# IPM_12V_12V.net
KiCad netlist of a schematic drawn in EasyEDA Pro
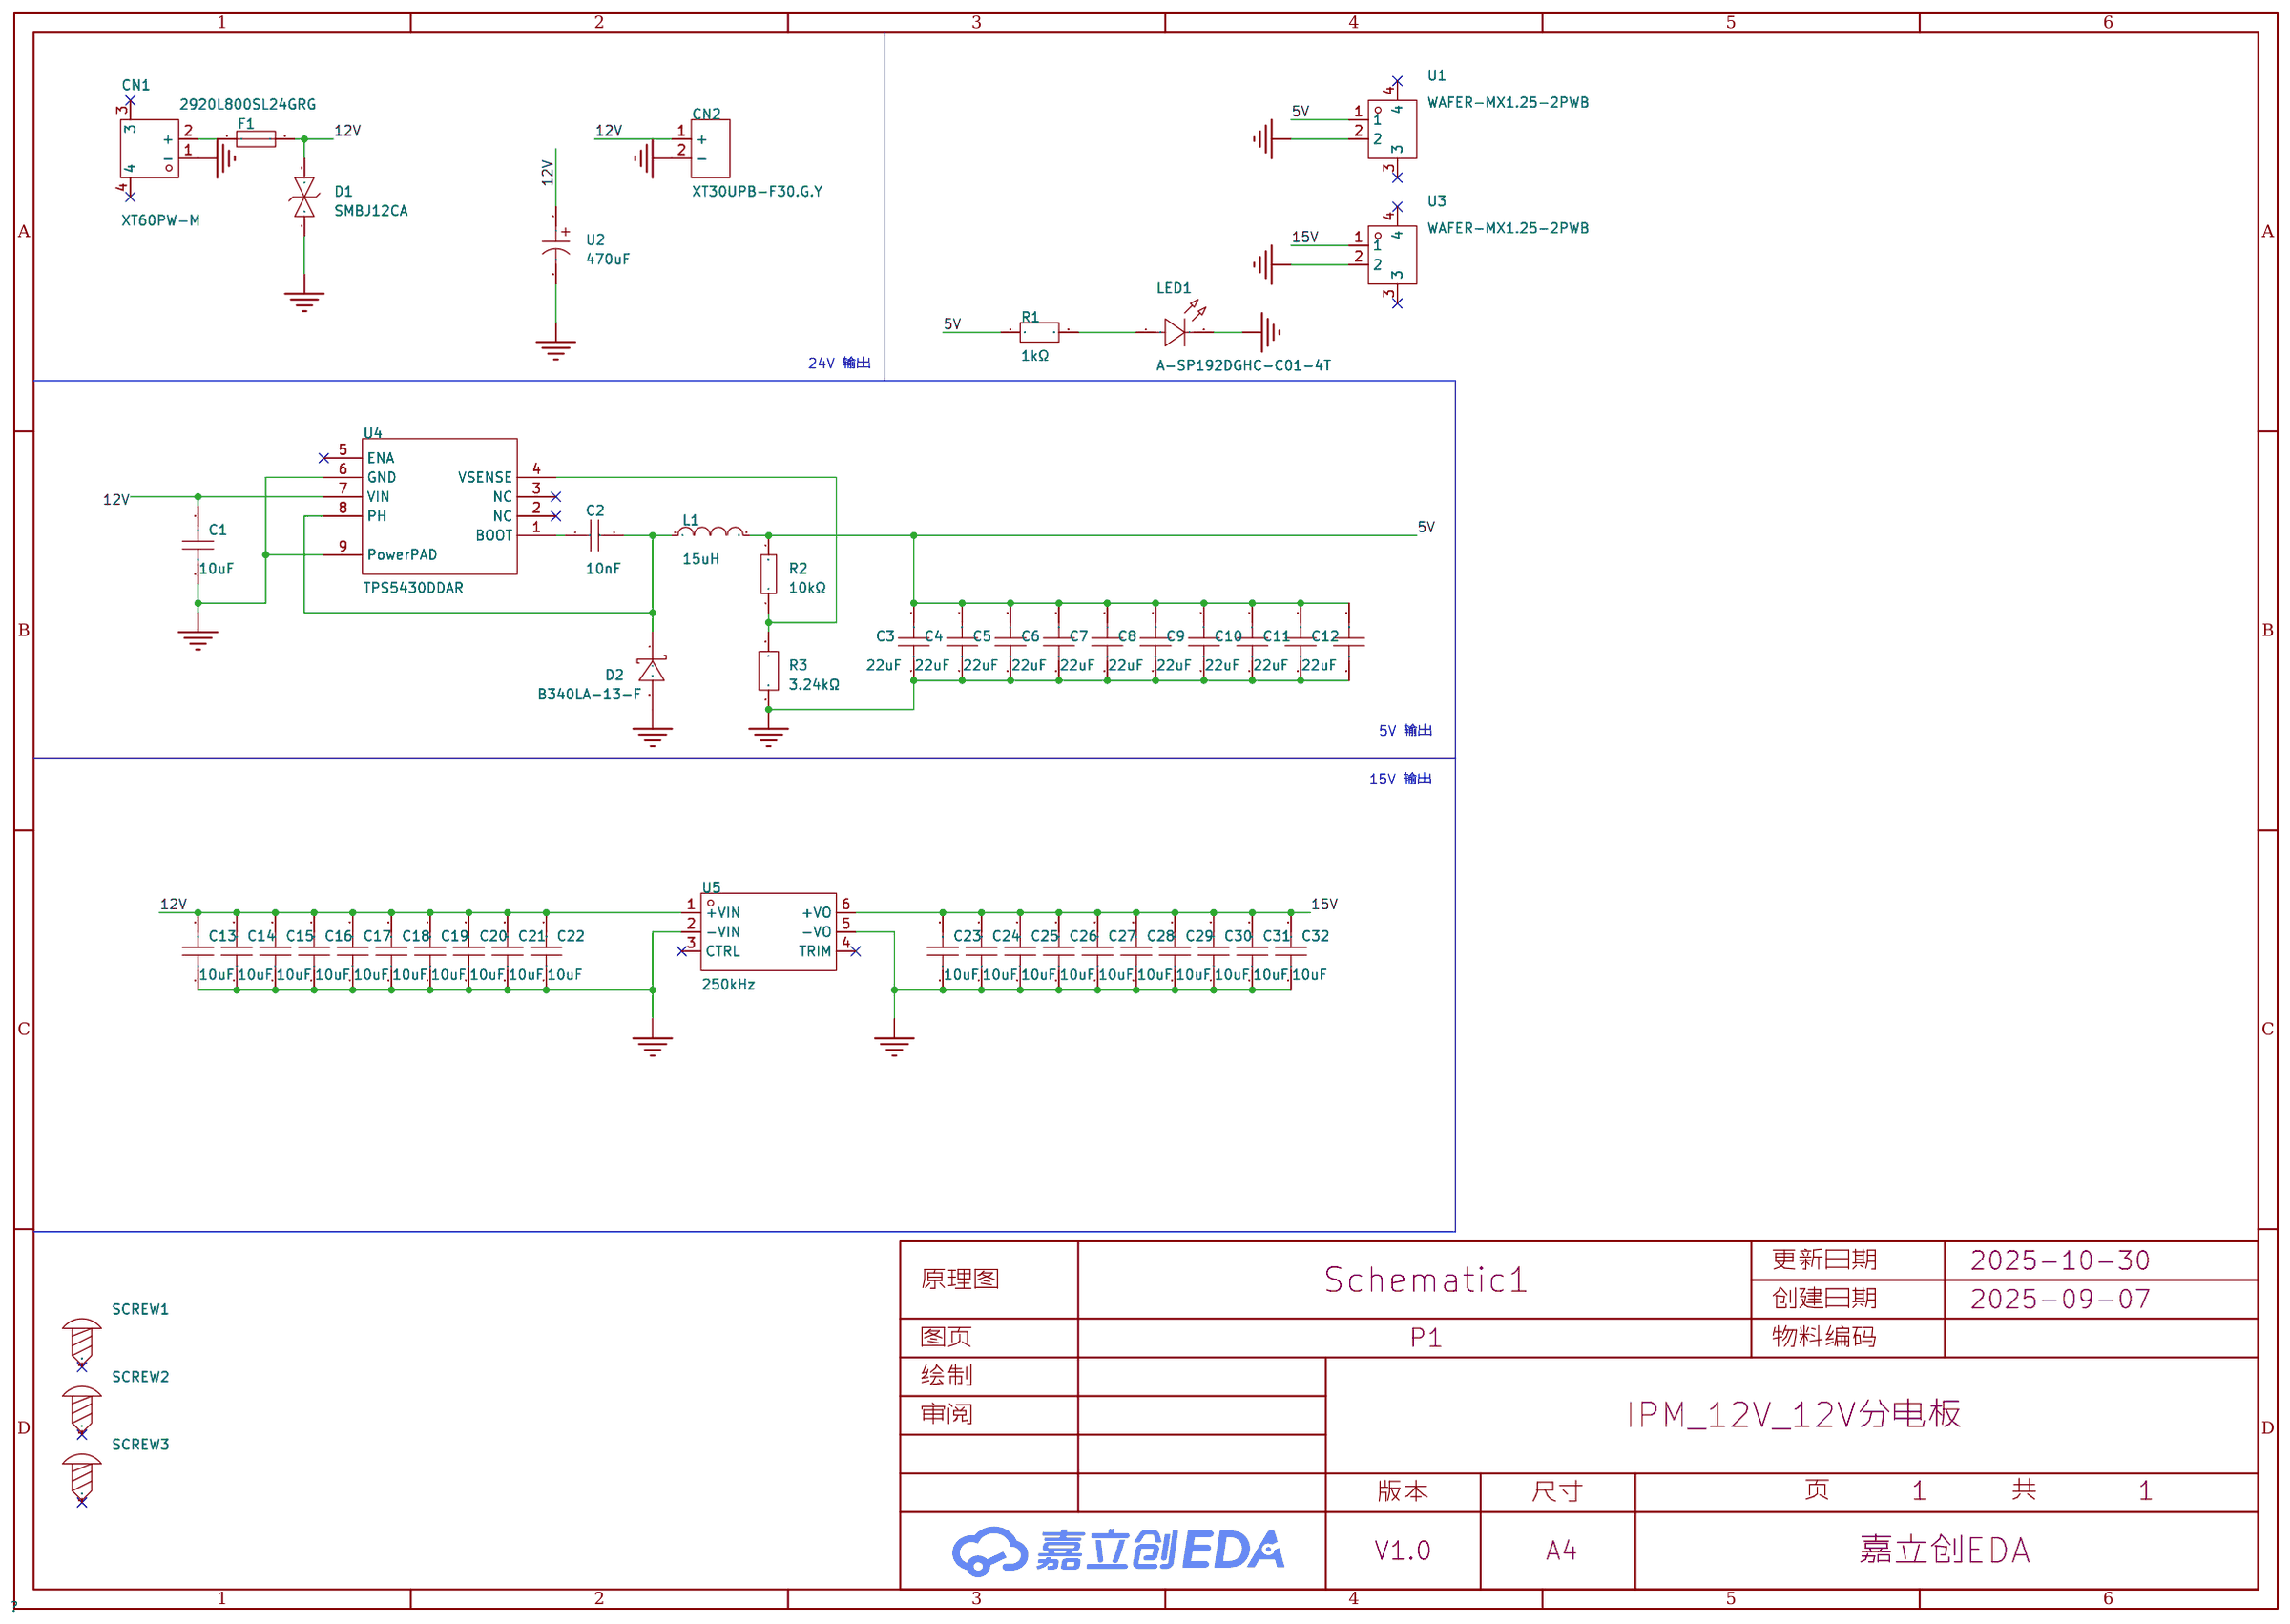
[diagram p0: schematic sheet]

(export (version "E")
  (design (tool "Eeschema 10.0.6"))
  (components
    (comp (ref "C1")
      (value "10uF")
      (footprint "easyedapro:C1206")
      (description "容值:10uF;精度:±10%;额定电压:50V;温度系数:X7R;")
      (fields
        (field (name "Manufacturer Part") "CL31B106KBHNNNE")
        (field (name "Manufacturer") "SAMSUNG(三星)")
      )
      (libsource (lib "easyedapro") (part "CL31B106KBHNNNE"))
    )
    (comp (ref "C2")
      (value "10nF")
      (footprint "easyedapro:C0603")
      (description "容值:10nF;精度:±10%;额定电压:50V;温度系数:X7R;")
      (fields
        (field (name "Manufacturer Part") "CL10B103KB8NNNC")
        (field (name "Manufacturer") "SAMSUNG(三星)")
      )
      (libsource (lib "easyedapro") (part "CL10B103KB8NNNC"))
    )
    (comp (ref "C3")
      (value "22uF")
      (footprint "easyedapro:C0603")
      (description "容值:22uF;精度:±20%;额定电压:16V;温度系数:X5R;")
      (fields
        (field (name "Manufacturer Part") "CL10A226MO7JZNC")
        (field (name "Manufacturer") "SAMSUNG(三星)")
      )
      (libsource (lib "easyedapro") (part "CL10A226MO7JZNC"))
    )
    (comp (ref "C4")
      (value "22uF")
      (footprint "easyedapro:C0603")
      (description "容值:22uF;精度:±20%;额定电压:16V;温度系数:X5R;")
      (fields
        (field (name "Manufacturer Part") "CL10A226MO7JZNC")
        (field (name "Manufacturer") "SAMSUNG(三星)")
      )
      (libsource (lib "easyedapro") (part "CL10A226MO7JZNC"))
    )
    (comp (ref "C5")
      (value "22uF")
      (footprint "easyedapro:C0603")
      (description "容值:22uF;精度:±20%;额定电压:16V;温度系数:X5R;")
      (fields
        (field (name "Manufacturer Part") "CL10A226MO7JZNC")
        (field (name "Manufacturer") "SAMSUNG(三星)")
      )
      (libsource (lib "easyedapro") (part "CL10A226MO7JZNC"))
    )
    (comp (ref "C6")
      (value "22uF")
      (footprint "easyedapro:C0603")
      (description "容值:22uF;精度:±20%;额定电压:16V;温度系数:X5R;")
      (fields
        (field (name "Manufacturer Part") "CL10A226MO7JZNC")
        (field (name "Manufacturer") "SAMSUNG(三星)")
      )
      (libsource (lib "easyedapro") (part "CL10A226MO7JZNC"))
    )
    (comp (ref "C7")
      (value "22uF")
      (footprint "easyedapro:C0603")
      (description "容值:22uF;精度:±20%;额定电压:16V;温度系数:X5R;")
      (fields
        (field (name "Manufacturer Part") "CL10A226MO7JZNC")
        (field (name "Manufacturer") "SAMSUNG(三星)")
      )
      (libsource (lib "easyedapro") (part "CL10A226MO7JZNC"))
    )
    (comp (ref "C8")
      (value "22uF")
      (footprint "easyedapro:C0603")
      (description "容值:22uF;精度:±20%;额定电压:16V;温度系数:X5R;")
      (fields
        (field (name "Manufacturer Part") "CL10A226MO7JZNC")
        (field (name "Manufacturer") "SAMSUNG(三星)")
      )
      (libsource (lib "easyedapro") (part "CL10A226MO7JZNC"))
    )
    (comp (ref "C9")
      (value "22uF")
      (footprint "easyedapro:C0603")
      (description "容值:22uF;精度:±20%;额定电压:16V;温度系数:X5R;")
      (fields
        (field (name "Manufacturer Part") "CL10A226MO7JZNC")
        (field (name "Manufacturer") "SAMSUNG(三星)")
      )
      (libsource (lib "easyedapro") (part "CL10A226MO7JZNC"))
    )
    (comp (ref "C10")
      (value "22uF")
      (footprint "easyedapro:C0603")
      (description "容值:22uF;精度:±20%;额定电压:16V;温度系数:X5R;")
      (fields
        (field (name "Manufacturer Part") "CL10A226MO7JZNC")
        (field (name "Manufacturer") "SAMSUNG(三星)")
      )
      (libsource (lib "easyedapro") (part "CL10A226MO7JZNC"))
    )
    (comp (ref "C11")
      (value "22uF")
      (footprint "easyedapro:C0603")
      (description "容值:22uF;精度:±20%;额定电压:16V;温度系数:X5R;")
      (fields
        (field (name "Manufacturer Part") "CL10A226MO7JZNC")
        (field (name "Manufacturer") "SAMSUNG(三星)")
      )
      (libsource (lib "easyedapro") (part "CL10A226MO7JZNC"))
    )
    (comp (ref "C12")
      (value "22uF")
      (footprint "easyedapro:C0603")
      (description "容值:22uF;精度:±20%;额定电压:16V;温度系数:X5R;")
      (fields
        (field (name "Manufacturer Part") "CL10A226MO7JZNC")
        (field (name "Manufacturer") "SAMSUNG(三星)")
      )
      (libsource (lib "easyedapro") (part "CL10A226MO7JZNC"))
    )
    (comp (ref "C13")
      (value "10uF")
      (footprint "easyedapro:C1206")
      (description "容值:10uF;精度:±10%;额定电压:50V;温度系数:X7R;")
      (fields
        (field (name "Manufacturer Part") "CL31B106KBHNNNE")
        (field (name "Manufacturer") "SAMSUNG(三星)")
      )
      (libsource (lib "easyedapro") (part "CL31B106KBHNNNE"))
    )
    (comp (ref "C14")
      (value "10uF")
      (footprint "easyedapro:C1206")
      (description "容值:10uF;精度:±10%;额定电压:50V;温度系数:X7R;")
      (fields
        (field (name "Manufacturer Part") "CL31B106KBHNNNE")
        (field (name "Manufacturer") "SAMSUNG(三星)")
      )
      (libsource (lib "easyedapro") (part "CL31B106KBHNNNE"))
    )
    (comp (ref "C15")
      (value "10uF")
      (footprint "easyedapro:C1206")
      (description "容值:10uF;精度:±10%;额定电压:50V;温度系数:X7R;")
      (fields
        (field (name "Manufacturer Part") "CL31B106KBHNNNE")
        (field (name "Manufacturer") "SAMSUNG(三星)")
      )
      (libsource (lib "easyedapro") (part "CL31B106KBHNNNE"))
    )
    (comp (ref "C16")
      (value "10uF")
      (footprint "easyedapro:C1206")
      (description "容值:10uF;精度:±10%;额定电压:50V;温度系数:X7R;")
      (fields
        (field (name "Manufacturer Part") "CL31B106KBHNNNE")
        (field (name "Manufacturer") "SAMSUNG(三星)")
      )
      (libsource (lib "easyedapro") (part "CL31B106KBHNNNE"))
    )
    (comp (ref "C17")
      (value "10uF")
      (footprint "easyedapro:C1206")
      (description "容值:10uF;精度:±10%;额定电压:50V;温度系数:X7R;")
      (fields
        (field (name "Manufacturer Part") "CL31B106KBHNNNE")
        (field (name "Manufacturer") "SAMSUNG(三星)")
      )
      (libsource (lib "easyedapro") (part "CL31B106KBHNNNE"))
    )
    (comp (ref "C18")
      (value "10uF")
      (footprint "easyedapro:C1206")
      (description "容值:10uF;精度:±10%;额定电压:50V;温度系数:X7R;")
      (fields
        (field (name "Manufacturer Part") "CL31B106KBHNNNE")
        (field (name "Manufacturer") "SAMSUNG(三星)")
      )
      (libsource (lib "easyedapro") (part "CL31B106KBHNNNE"))
    )
    (comp (ref "C19")
      (value "10uF")
      (footprint "easyedapro:C1206")
      (description "容值:10uF;精度:±10%;额定电压:50V;温度系数:X7R;")
      (fields
        (field (name "Manufacturer Part") "CL31B106KBHNNNE")
        (field (name "Manufacturer") "SAMSUNG(三星)")
      )
      (libsource (lib "easyedapro") (part "CL31B106KBHNNNE"))
    )
    (comp (ref "C20")
      (value "10uF")
      (footprint "easyedapro:C1206")
      (description "容值:10uF;精度:±10%;额定电压:50V;温度系数:X7R;")
      (fields
        (field (name "Manufacturer Part") "CL31B106KBHNNNE")
        (field (name "Manufacturer") "SAMSUNG(三星)")
      )
      (libsource (lib "easyedapro") (part "CL31B106KBHNNNE"))
    )
    (comp (ref "C21")
      (value "10uF")
      (footprint "easyedapro:C1206")
      (description "容值:10uF;精度:±10%;额定电压:50V;温度系数:X7R;")
      (fields
        (field (name "Manufacturer Part") "CL31B106KBHNNNE")
        (field (name "Manufacturer") "SAMSUNG(三星)")
      )
      (libsource (lib "easyedapro") (part "CL31B106KBHNNNE"))
    )
    (comp (ref "C22")
      (value "10uF")
      (footprint "easyedapro:C1206")
      (description "容值:10uF;精度:±10%;额定电压:50V;温度系数:X7R;")
      (fields
        (field (name "Manufacturer Part") "CL31B106KBHNNNE")
        (field (name "Manufacturer") "SAMSUNG(三星)")
      )
      (libsource (lib "easyedapro") (part "CL31B106KBHNNNE"))
    )
    (comp (ref "C23")
      (value "10uF")
      (footprint "easyedapro:C1206")
      (description "容值:10uF;精度:±10%;额定电压:50V;温度系数:X7R;")
      (fields
        (field (name "Manufacturer Part") "CL31B106KBHNNNE")
        (field (name "Manufacturer") "SAMSUNG(三星)")
      )
      (libsource (lib "easyedapro") (part "CL31B106KBHNNNE"))
    )
    (comp (ref "C24")
      (value "10uF")
      (footprint "easyedapro:C1206")
      (description "容值:10uF;精度:±10%;额定电压:50V;温度系数:X7R;")
      (fields
        (field (name "Manufacturer Part") "CL31B106KBHNNNE")
        (field (name "Manufacturer") "SAMSUNG(三星)")
      )
      (libsource (lib "easyedapro") (part "CL31B106KBHNNNE"))
    )
    (comp (ref "C25")
      (value "10uF")
      (footprint "easyedapro:C1206")
      (description "容值:10uF;精度:±10%;额定电压:50V;温度系数:X7R;")
      (fields
        (field (name "Manufacturer Part") "CL31B106KBHNNNE")
        (field (name "Manufacturer") "SAMSUNG(三星)")
      )
      (libsource (lib "easyedapro") (part "CL31B106KBHNNNE"))
    )
    (comp (ref "C26")
      (value "10uF")
      (footprint "easyedapro:C1206")
      (description "容值:10uF;精度:±10%;额定电压:50V;温度系数:X7R;")
      (fields
        (field (name "Manufacturer Part") "CL31B106KBHNNNE")
        (field (name "Manufacturer") "SAMSUNG(三星)")
      )
      (libsource (lib "easyedapro") (part "CL31B106KBHNNNE"))
    )
    (comp (ref "C27")
      (value "10uF")
      (footprint "easyedapro:C1206")
      (description "容值:10uF;精度:±10%;额定电压:50V;温度系数:X7R;")
      (fields
        (field (name "Manufacturer Part") "CL31B106KBHNNNE")
        (field (name "Manufacturer") "SAMSUNG(三星)")
      )
      (libsource (lib "easyedapro") (part "CL31B106KBHNNNE"))
    )
    (comp (ref "C28")
      (value "10uF")
      (footprint "easyedapro:C1206")
      (description "容值:10uF;精度:±10%;额定电压:50V;温度系数:X7R;")
      (fields
        (field (name "Manufacturer Part") "CL31B106KBHNNNE")
        (field (name "Manufacturer") "SAMSUNG(三星)")
      )
      (libsource (lib "easyedapro") (part "CL31B106KBHNNNE"))
    )
    (comp (ref "C29")
      (value "10uF")
      (footprint "easyedapro:C1206")
      (description "容值:10uF;精度:±10%;额定电压:50V;温度系数:X7R;")
      (fields
        (field (name "Manufacturer Part") "CL31B106KBHNNNE")
        (field (name "Manufacturer") "SAMSUNG(三星)")
      )
      (libsource (lib "easyedapro") (part "CL31B106KBHNNNE"))
    )
    (comp (ref "C30")
      (value "10uF")
      (footprint "easyedapro:C1206")
      (description "容值:10uF;精度:±10%;额定电压:50V;温度系数:X7R;")
      (fields
        (field (name "Manufacturer Part") "CL31B106KBHNNNE")
        (field (name "Manufacturer") "SAMSUNG(三星)")
      )
      (libsource (lib "easyedapro") (part "CL31B106KBHNNNE"))
    )
    (comp (ref "C31")
      (value "10uF")
      (footprint "easyedapro:C1206")
      (description "容值:10uF;精度:±10%;额定电压:50V;温度系数:X7R;")
      (fields
        (field (name "Manufacturer Part") "CL31B106KBHNNNE")
        (field (name "Manufacturer") "SAMSUNG(三星)")
      )
      (libsource (lib "easyedapro") (part "CL31B106KBHNNNE"))
    )
    (comp (ref "C32")
      (value "10uF")
      (footprint "easyedapro:C1206")
      (description "容值:10uF;精度:±10%;额定电压:50V;温度系数:X7R;")
      (fields
        (field (name "Manufacturer Part") "CL31B106KBHNNNE")
        (field (name "Manufacturer") "SAMSUNG(三星)")
      )
      (libsource (lib "easyedapro") (part "CL31B106KBHNNNE"))
    )
    (comp (ref "CN1")
      (value "XT60PW-M")
      (footprint "easyedapro:CONN-TH_XT60PW-M")
      (description "类别:-;类型1:-;")
      (fields (field (name "Manufacturer") "AMASS(艾迈斯)"))
      (libsource (lib "easyedapro") (part "XT60PW-M"))
    )
    (comp (ref "CN2")
      (value "XT30UPB-F30.G.Y")
      (footprint "easyedapro:CONN-TH_XT30UPB-F")
      (description "类别:-;类型1:-;")
      (fields (field (name "Manufacturer") "AMASS(艾迈斯)"))
      (libsource (lib "easyedapro") (part "XT30UPB-F"))
    )
    (comp (ref "D1")
      (value "SMBJ12CA")
      (footprint "easyedapro:SMB_L4.6-W3.6-LS5.4-BI")
      (fields (field (name "Manufacturer") "R+O(宏嘉诚)"))
      (libsource (lib "easyedapro") (part "SMBJ12CA_C19077566"))
    )
    (comp (ref "D2")
      (value "B340LA-13-F")
      (footprint "easyedapro:SMA_L4.3-W2.6-LS5.2-RD")
      (description "正向压降(Vf):450mV@3A;直流反向耐压(Vr):40V;平均整流电流(Io):3A;")
      (fields (field (name "Manufacturer") "DIODES(美台)"))
      (libsource (lib "easyedapro") (part "B340LA-13-F"))
    )
    (comp (ref "F1")
      (value "2920L800SL24GRG")
      (footprint "easyedapro:F2920")
      (description "耐压(Vmax):24V;最大电流(Imax):50A;保持电流(Ihold):8A;跳闸电流(Itrip):16A;")
      (fields (field (name "Manufacturer") "LUTE(陆特)"))
      (libsource (lib "easyedapro") (part "2920L800SL24GRG"))
    )
    (comp (ref "L1")
      (value "15uH")
      (footprint "easyedapro:IND-SMD_L7.0-W6.6_FXL0630")
      (description "电感值:15uH;精度:±20%;额定电流:3A;饱和电流(Isat):4A;类型:一体成型电感;")
      (fields (field (name "Manufacturer Part") "FXL0630-150-M") (field (name "Manufacturer") "cjiang(长江微电)"))
      (libsource (lib "easyedapro") (part "FXL0630-150-M"))
    )
    (comp (ref "LED1")
      (value "A-SP192DGHC-C01-4T")
      (footprint "easyedapro:LED0603-FD")
      (fields (field (name "Manufacturer") "Amicc(欧密格光电)"))
      (libsource (lib "easyedapro") (part "A-SP192DGHC-C01-4T"))
    )
    (comp (ref "R1")
      (value "1kΩ")
      (footprint "easyedapro:R0603")
      (description "电阻类型:厚膜电阻;阻值:1kΩ;精度:±1%;功率:100mW;工作电压:75V;温度系数:±100ppm/°C;")
      (fields (field (name "Manufacturer Part") "FRC0603F1001TS") (field (name "Manufacturer") "FOJAN(富捷)"))
      (libsource (lib "easyedapro") (part "FRC0603F1001TS"))
    )
    (comp (ref "R2")
      (value "10kΩ")
      (footprint "easyedapro:R0603")
      (description "电阻类型:厚膜电阻;阻值:10kΩ;精度:±1%;功率:100mW;工作电压:75V;温度系数:±100ppm/°C;")
      (fields
        (field (name "Manufacturer Part") "0603WAF1002T5E")
        (field (name "Manufacturer") "UNI-ROYAL(厚声)")
      )
      (libsource (lib "easyedapro") (part "0603WAF1002T5E"))
    )
    (comp (ref "R3")
      (value "3.24kΩ")
      (footprint "easyedapro:R0603")
      (description "电阻类型:厚膜电阻;阻值:3.24kΩ;精度:±1%;功率:100mW;工作电压:75V;温度系数:±100ppm/°C;")
      (fields (field (name "Manufacturer Part") "FRC0603F3241TS") (field (name "Manufacturer") "FOJAN(富捷)"))
      (libsource (lib "easyedapro") (part "FRC0603F3241TS"))
    )
    (comp (ref "SCREW1")
      (value "~")
      (footprint "easyedapro:M2螺丝")
      (libsource (lib "easyedapro") (part "螺丝孔"))
    )
    (comp (ref "SCREW2")
      (value "~")
      (footprint "easyedapro:M2螺丝")
      (libsource (lib "easyedapro") (part "螺丝孔"))
    )
    (comp (ref "SCREW3")
      (value "~")
      (footprint "easyedapro:M2螺丝")
      (libsource (lib "easyedapro") (part "螺丝孔"))
    )
    (comp (ref "U1")
      (value "WAFER-MX1.25-2PWB")
      (footprint "easyedapro:CONN-SMD_2P-P1.25_XUNPU_WAFER-MX1.25-2PWB")
      (fields (field (name "Manufacturer") "XUNPU(讯普)"))
      (libsource (lib "easyedapro") (part "WAFER-MX1.25-2PWB"))
    )
    (comp (ref "U2")
      (value "470uF")
      (footprint "easyedapro:CAP-TH_BD10.0-P5.00-D1.0-FD")
      (description "容值:470uF;精度:±20%;额定电压:50V;纹波电流:-;等效串联电阻(ESR):-;")
      (fields
        (field (name "Manufacturer Part") "ERJ1HM471G16C36T")
        (field (name "Manufacturer") "AISHI(艾华集团)")
      )
      (libsource (lib "easyedapro") (part "ERJ1HM471G16C36T"))
    )
    (comp (ref "U3")
      (value "WAFER-MX1.25-2PWB")
      (footprint "easyedapro:CONN-SMD_2P-P1.25_XUNPU_WAFER-MX1.25-2PWB")
      (fields (field (name "Manufacturer") "XUNPU(讯普)"))
      (libsource (lib "easyedapro") (part "WAFER-MX1.25-2PWB"))
    )
    (comp (ref "U4")
      (value "TPS5430DDAR")
      (footprint "easyedapro:ESOP-8_L4.9-W3.9-P1.27-LS6.0-TL-EP")
      (description "功能类型:降压型;输出类型:可调;工作电压:5.5V~36V;输出电压:1.221V~32.04V;输出电流:3A;")
      (fields (field (name "Manufacturer") "TI(德州仪器)"))
      (libsource (lib "easyedapro") (part "TPS5430DDAR"))
    )
    (comp (ref "U5")
      (value "250kHz")
      (footprint "easyedapro:PWRM-TH_URB2415LD-30WR3")
      (fields (field (name "Manufacturer Part") "URB2415LD-30WR3") (field (name "Manufacturer") "YLPTEC(易川)"))
      (libsource (lib "easyedapro") (part "URB2415LD-30WR3_C5369835"))
    )
  )
  (nets
    (net (code "1") (name "/5V") (class "Default")
      (node (ref "C10") (pin "1") (pinfunction "1_1") (pintype "unspecified"))
      (node (ref "C11") (pin "1") (pinfunction "1_1") (pintype "unspecified"))
      (node (ref "C12") (pin "1") (pinfunction "1_1") (pintype "unspecified"))
      (node (ref "C3") (pin "1") (pinfunction "1_1") (pintype "unspecified"))
      (node (ref "C4") (pin "1") (pinfunction "1_1") (pintype "unspecified"))
      (node (ref "C5") (pin "1") (pinfunction "1_1") (pintype "unspecified"))
      (node (ref "C6") (pin "1") (pinfunction "1_1") (pintype "unspecified"))
      (node (ref "C7") (pin "1") (pinfunction "1_1") (pintype "unspecified"))
      (node (ref "C8") (pin "1") (pinfunction "1_1") (pintype "unspecified"))
      (node (ref "C9") (pin "1") (pinfunction "1_1") (pintype "unspecified"))
      (node (ref "L1") (pin "2") (pinfunction "2_2") (pintype "unspecified"))
      (node (ref "R1") (pin "1") (pinfunction "1_1") (pintype "unspecified"))
      (node (ref "R2") (pin "2") (pinfunction "2_2") (pintype "input"))
      (node (ref "U1") (pin "1") (pinfunction "1_1") (pintype "unspecified"))
    )
    (net (code "2") (name "/12V") (class "Default")
      (node (ref "C1") (pin "2") (pinfunction "2_2") (pintype "unspecified"))
      (node (ref "C13") (pin "2") (pinfunction "2_2") (pintype "unspecified"))
      (node (ref "C14") (pin "2") (pinfunction "2_2") (pintype "unspecified"))
      (node (ref "C15") (pin "2") (pinfunction "2_2") (pintype "unspecified"))
      (node (ref "C16") (pin "2") (pinfunction "2_2") (pintype "unspecified"))
      (node (ref "C17") (pin "2") (pinfunction "2_2") (pintype "unspecified"))
      (node (ref "C18") (pin "2") (pinfunction "2_2") (pintype "unspecified"))
      (node (ref "C19") (pin "2") (pinfunction "2_2") (pintype "unspecified"))
      (node (ref "C20") (pin "2") (pinfunction "2_2") (pintype "unspecified"))
      (node (ref "C21") (pin "2") (pinfunction "2_2") (pintype "unspecified"))
      (node (ref "C22") (pin "2") (pinfunction "2_2") (pintype "unspecified"))
      (node (ref "CN2") (pin "1") (pinfunction "+_1") (pintype "unspecified"))
      (node (ref "D1") (pin "2") (pinfunction "2_2") (pintype "unspecified"))
      (node (ref "F1") (pin "2") (pinfunction "2_2") (pintype "unspecified"))
      (node (ref "U2") (pin "1") (pinfunction "1_1") (pintype "input"))
      (node (ref "U4") (pin "7") (pinfunction "VIN_7") (pintype "unspecified"))
      (node (ref "U5") (pin "1") (pinfunction "+VIN_1") (pintype "unspecified"))
    )
    (net (code "3") (name "/15V") (class "Default")
      (node (ref "C23") (pin "2") (pinfunction "2_2") (pintype "unspecified"))
      (node (ref "C24") (pin "2") (pinfunction "2_2") (pintype "unspecified"))
      (node (ref "C25") (pin "2") (pinfunction "2_2") (pintype "unspecified"))
      (node (ref "C26") (pin "2") (pinfunction "2_2") (pintype "unspecified"))
      (node (ref "C27") (pin "2") (pinfunction "2_2") (pintype "unspecified"))
      (node (ref "C28") (pin "2") (pinfunction "2_2") (pintype "unspecified"))
      (node (ref "C29") (pin "2") (pinfunction "2_2") (pintype "unspecified"))
      (node (ref "C30") (pin "2") (pinfunction "2_2") (pintype "unspecified"))
      (node (ref "C31") (pin "2") (pinfunction "2_2") (pintype "unspecified"))
      (node (ref "C32") (pin "2") (pinfunction "2_2") (pintype "unspecified"))
      (node (ref "U3") (pin "1") (pinfunction "1_1") (pintype "unspecified"))
      (node (ref "U5") (pin "6") (pinfunction "+VO_6") (pintype "unspecified"))
    )
    (net (code "4") (name "GND") (class "Default")
      (node (ref "C1") (pin "1") (pinfunction "1_1") (pintype "unspecified"))
      (node (ref "C10") (pin "2") (pinfunction "2_2") (pintype "unspecified"))
      (node (ref "C11") (pin "2") (pinfunction "2_2") (pintype "unspecified"))
      (node (ref "C12") (pin "2") (pinfunction "2_2") (pintype "unspecified"))
      (node (ref "C13") (pin "1") (pinfunction "1_1") (pintype "unspecified"))
      (node (ref "C14") (pin "1") (pinfunction "1_1") (pintype "unspecified"))
      (node (ref "C15") (pin "1") (pinfunction "1_1") (pintype "unspecified"))
      (node (ref "C16") (pin "1") (pinfunction "1_1") (pintype "unspecified"))
      (node (ref "C17") (pin "1") (pinfunction "1_1") (pintype "unspecified"))
      (node (ref "C18") (pin "1") (pinfunction "1_1") (pintype "unspecified"))
      (node (ref "C19") (pin "1") (pinfunction "1_1") (pintype "unspecified"))
      (node (ref "C20") (pin "1") (pinfunction "1_1") (pintype "unspecified"))
      (node (ref "C21") (pin "1") (pinfunction "1_1") (pintype "unspecified"))
      (node (ref "C22") (pin "1") (pinfunction "1_1") (pintype "unspecified"))
      (node (ref "C23") (pin "1") (pinfunction "1_1") (pintype "unspecified"))
      (node (ref "C24") (pin "1") (pinfunction "1_1") (pintype "unspecified"))
      (node (ref "C25") (pin "1") (pinfunction "1_1") (pintype "unspecified"))
      (node (ref "C26") (pin "1") (pinfunction "1_1") (pintype "unspecified"))
      (node (ref "C27") (pin "1") (pinfunction "1_1") (pintype "unspecified"))
      (node (ref "C28") (pin "1") (pinfunction "1_1") (pintype "unspecified"))
      (node (ref "C29") (pin "1") (pinfunction "1_1") (pintype "unspecified"))
      (node (ref "C3") (pin "2") (pinfunction "2_2") (pintype "unspecified"))
      (node (ref "C30") (pin "1") (pinfunction "1_1") (pintype "unspecified"))
      (node (ref "C31") (pin "1") (pinfunction "1_1") (pintype "unspecified"))
      (node (ref "C32") (pin "1") (pinfunction "1_1") (pintype "unspecified"))
      (node (ref "C4") (pin "2") (pinfunction "2_2") (pintype "unspecified"))
      (node (ref "C5") (pin "2") (pinfunction "2_2") (pintype "unspecified"))
      (node (ref "C6") (pin "2") (pinfunction "2_2") (pintype "unspecified"))
      (node (ref "C7") (pin "2") (pinfunction "2_2") (pintype "unspecified"))
      (node (ref "C8") (pin "2") (pinfunction "2_2") (pintype "unspecified"))
      (node (ref "C9") (pin "2") (pinfunction "2_2") (pintype "unspecified"))
      (node (ref "CN1") (pin "1") (pinfunction "-_1") (pintype "unspecified"))
      (node (ref "CN2") (pin "2") (pinfunction "-_2") (pintype "unspecified"))
      (node (ref "D1") (pin "1") (pinfunction "1_1") (pintype "unspecified"))
      (node (ref "D2") (pin "2") (pinfunction "A_2") (pintype "unspecified"))
      (node (ref "LED1") (pin "2") (pinfunction "K_2") (pintype "unspecified"))
      (node (ref "R3") (pin "1") (pinfunction "1_1") (pintype "unspecified"))
      (node (ref "U1") (pin "2") (pinfunction "2_2") (pintype "unspecified"))
      (node (ref "U2") (pin "2") (pinfunction "2_2") (pintype "input"))
      (node (ref "U3") (pin "2") (pinfunction "2_2") (pintype "unspecified"))
      (node (ref "U4") (pin "6") (pinfunction "GND_6") (pintype "unspecified"))
      (node (ref "U4") (pin "9") (pinfunction "PowerPAD_9") (pintype "unspecified"))
      (node (ref "U5") (pin "2") (pinfunction "-VIN_2") (pintype "unspecified"))
      (node (ref "U5") (pin "5") (pinfunction "-VO_5") (pintype "unspecified"))
    )
    (net (code "5") (name "Net-(CN1-+)") (class "Default")
      (node (ref "CN1") (pin "2") (pinfunction "+_2") (pintype "unspecified"))
      (node (ref "F1") (pin "1") (pinfunction "1_1") (pintype "unspecified"))
    )
    (net (code "6") (name "Net-(D2-K)") (class "Default")
      (node (ref "C2") (pin "2") (pinfunction "2_2") (pintype "input"))
      (node (ref "D2") (pin "1") (pinfunction "K_1") (pintype "unspecified"))
      (node (ref "L1") (pin "1") (pinfunction "1_1") (pintype "unspecified"))
      (node (ref "U4") (pin "8") (pinfunction "PH_8") (pintype "unspecified"))
    )
    (net (code "7") (name "Net-(LED1-A)") (class "Default")
      (node (ref "LED1") (pin "1") (pinfunction "A_1") (pintype "unspecified"))
      (node (ref "R1") (pin "2") (pinfunction "2_2") (pintype "unspecified"))
    )
    (net (code "8") (name "Net-(U4-BOOT)") (class "Default")
      (node (ref "C2") (pin "1") (pinfunction "1_1") (pintype "input"))
      (node (ref "U4") (pin "1") (pinfunction "BOOT_1") (pintype "unspecified"))
    )
    (net (code "9") (name "Net-(U4-VSENSE)") (class "Default")
      (node (ref "R2") (pin "1") (pinfunction "1_1") (pintype "input"))
      (node (ref "R3") (pin "2") (pinfunction "2_2") (pintype "unspecified"))
      (node (ref "U4") (pin "4") (pinfunction "VSENSE_4") (pintype "unspecified"))
    )
    (net (code "10") (name "unconnected-(CN1-Pad3)") (class "Default")
      (node (ref "CN1") (pin "3") (pinfunction "3_3") (pintype "unspecified+no_connect"))
    )
    (net (code "11") (name "unconnected-(CN1-Pad4)") (class "Default")
      (node (ref "CN1") (pin "4") (pinfunction "4_4") (pintype "unspecified+no_connect"))
    )
    (net (code "12") (name "unconnected-(SCREW1-Pad1)") (class "Default")
      (node (ref "SCREW1") (pin "1") (pinfunction "1_1") (pintype "input+no_connect"))
    )
    (net (code "13") (name "unconnected-(SCREW2-Pad1)") (class "Default")
      (node (ref "SCREW2") (pin "1") (pinfunction "1_1") (pintype "input+no_connect"))
    )
    (net (code "14") (name "unconnected-(SCREW3-Pad1)") (class "Default")
      (node (ref "SCREW3") (pin "1") (pinfunction "1_1") (pintype "input+no_connect"))
    )
    (net (code "15") (name "unconnected-(U1-Pad3)") (class "Default")
      (node (ref "U1") (pin "3") (pinfunction "3_3") (pintype "unspecified+no_connect"))
    )
    (net (code "16") (name "unconnected-(U1-Pad4)") (class "Default")
      (node (ref "U1") (pin "4") (pinfunction "4_4") (pintype "unspecified+no_connect"))
    )
    (net (code "17") (name "unconnected-(U3-Pad3)") (class "Default")
      (node (ref "U3") (pin "3") (pinfunction "3_3") (pintype "unspecified+no_connect"))
    )
    (net (code "18") (name "unconnected-(U3-Pad4)") (class "Default")
      (node (ref "U3") (pin "4") (pinfunction "4_4") (pintype "unspecified+no_connect"))
    )
    (net (code "19") (name "unconnected-(U4-ENA-Pad5)") (class "Default")
      (node (ref "U4") (pin "5") (pinfunction "ENA_5") (pintype "unspecified+no_connect"))
    )
    (net (code "20") (name "unconnected-(U4-NC-Pad2)") (class "Default")
      (node (ref "U4") (pin "2") (pinfunction "NC_2") (pintype "unspecified+no_connect"))
    )
    (net (code "21") (name "unconnected-(U4-NC-Pad3)") (class "Default")
      (node (ref "U4") (pin "3") (pinfunction "NC_3") (pintype "unspecified+no_connect"))
    )
    (net (code "22") (name "unconnected-(U5-CTRL-Pad3)") (class "Default")
      (node (ref "U5") (pin "3") (pinfunction "CTRL_3") (pintype "unspecified+no_connect"))
    )
    (net (code "23") (name "unconnected-(U5-TRIM-Pad4)") (class "Default")
      (node (ref "U5") (pin "4") (pinfunction "TRIM_4") (pintype "unspecified+no_connect"))
    )
  )
)
